# PerfBoard.net
KiCad netlist of a schematic drawn in EAGLE
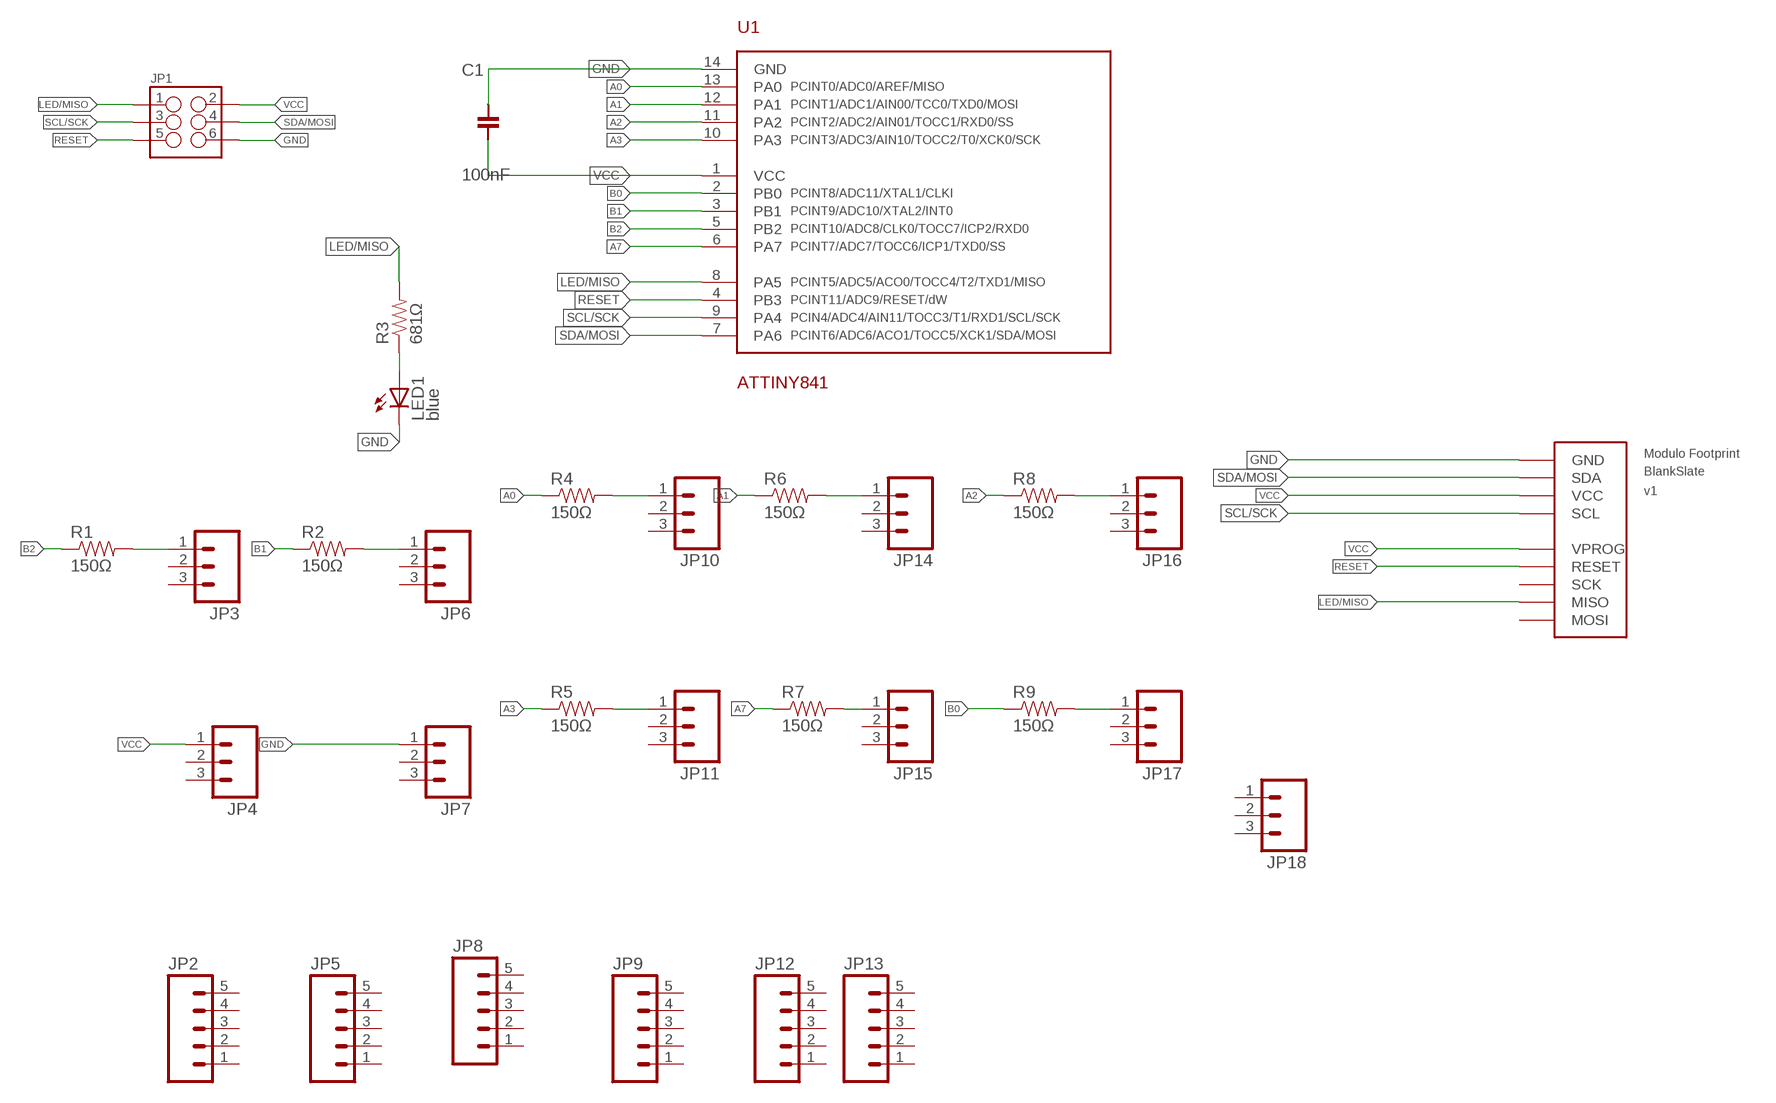
[diagram p0: schematic, sheet 1]

(export (version "E")
  (design (tool "Eeschema 10.0.6"))
  (components
    (comp (ref "C1")
      (value "100nF")
      (footprint "eagle-import:0603")
      (fields (field (name "PARTNUM") "C0603C104K5RACTU"))
      (libsource (lib "eagle-import") (part "CAPACITOR-100NF"))
    )
    (comp (ref "JP1")
      (value "M03X2")
      (footprint "eagle-import:2X3_SMD")
      (libsource (lib "eagle-import") (part "M03X2"))
    )
    (comp (ref "JP2")
      (value "M05NO_SILK")
      (footprint "eagle-import:1X05_NO_SILK")
      (libsource (lib "eagle-import") (part "M05NO_SILK"))
    )
    (comp (ref "JP3")
      (value "M031X03_NO_SILK")
      (footprint "eagle-import:1X03_NO_SILK")
      (libsource (lib "eagle-import") (part "M031X03_NO_SILK"))
    )
    (comp (ref "JP4")
      (value "M031X03_NO_SILK")
      (footprint "eagle-import:1X03_NO_SILK")
      (libsource (lib "eagle-import") (part "M031X03_NO_SILK"))
    )
    (comp (ref "JP5")
      (value "M05NO_SILK")
      (footprint "eagle-import:1X05_NO_SILK")
      (libsource (lib "eagle-import") (part "M05NO_SILK"))
    )
    (comp (ref "JP6")
      (value "M031X03_NO_SILK")
      (footprint "eagle-import:1X03_NO_SILK")
      (libsource (lib "eagle-import") (part "M031X03_NO_SILK"))
    )
    (comp (ref "JP7")
      (value "M031X03_NO_SILK")
      (footprint "eagle-import:1X03_NO_SILK")
      (libsource (lib "eagle-import") (part "M031X03_NO_SILK"))
    )
    (comp (ref "JP8")
      (value "M05NO_SILK")
      (footprint "eagle-import:1X05_NO_SILK")
      (libsource (lib "eagle-import") (part "M05NO_SILK"))
    )
    (comp (ref "JP9")
      (value "M05NO_SILK")
      (footprint "eagle-import:1X05_NO_SILK")
      (libsource (lib "eagle-import") (part "M05NO_SILK"))
    )
    (comp (ref "JP10")
      (value "M031X03_NO_SILK")
      (footprint "eagle-import:1X03_NO_SILK")
      (libsource (lib "eagle-import") (part "M031X03_NO_SILK"))
    )
    (comp (ref "JP11")
      (value "M031X03_NO_SILK")
      (footprint "eagle-import:1X03_NO_SILK")
      (libsource (lib "eagle-import") (part "M031X03_NO_SILK"))
    )
    (comp (ref "JP12")
      (value "M05NO_SILK")
      (footprint "eagle-import:1X05_NO_SILK")
      (libsource (lib "eagle-import") (part "M05NO_SILK"))
    )
    (comp (ref "JP13")
      (value "M05NO_SILK")
      (footprint "eagle-import:1X05_NO_SILK")
      (libsource (lib "eagle-import") (part "M05NO_SILK"))
    )
    (comp (ref "JP14")
      (value "M031X03_NO_SILK")
      (footprint "eagle-import:1X03_NO_SILK")
      (libsource (lib "eagle-import") (part "M031X03_NO_SILK"))
    )
    (comp (ref "JP15")
      (value "M031X03_NO_SILK")
      (footprint "eagle-import:1X03_NO_SILK")
      (libsource (lib "eagle-import") (part "M031X03_NO_SILK"))
    )
    (comp (ref "JP16")
      (value "M031X03_NO_SILK")
      (footprint "eagle-import:1X03_NO_SILK")
      (libsource (lib "eagle-import") (part "M031X03_NO_SILK"))
    )
    (comp (ref "JP17")
      (value "M031X03_NO_SILK")
      (footprint "eagle-import:1X03_NO_SILK")
      (libsource (lib "eagle-import") (part "M031X03_NO_SILK"))
    )
    (comp (ref "JP18")
      (value "M031X03_NO_SILK")
      (footprint "eagle-import:1X03_NO_SILK")
      (libsource (lib "eagle-import") (part "M031X03_NO_SILK"))
    )
    (comp (ref "LED1")
      (value "blue")
      (footprint "eagle-import:0805-LED")
      (fields (field (name "PARTNUM") "LTST-C171TBKT"))
      (libsource (lib "eagle-import") (part "LED-0805-BLUE"))
    )
    (comp (ref "PCB1")
      (value "EXCLUDE")
      (footprint "eagle-import:FOOTPRINT2")
      (fields (field (name "BOARD") "BlankSlate") (field (name "VERSION") "v1"))
      (libsource (lib "eagle-import") (part "FOOTPRINTFOOTPRINT-2"))
    )
    (comp (ref "R1")
      (value "150Ω")
      (footprint "eagle-import:0603")
      (fields (field (name "PARTNUM") "ERJ-3EKF1500V"))
      (libsource (lib "eagle-import") (part "RESISTOR-150Ω"))
    )
    (comp (ref "R2")
      (value "150Ω")
      (footprint "eagle-import:0603")
      (fields (field (name "PARTNUM") "ERJ-3EKF1500V"))
      (libsource (lib "eagle-import") (part "RESISTOR-150Ω"))
    )
    (comp (ref "R3")
      (value "681Ω")
      (footprint "eagle-import:0603")
      (fields (field (name "PARTNUM") "ERJ-3EKF6810V"))
      (libsource (lib "eagle-import") (part "RESISTOR-681Ω"))
    )
    (comp (ref "R4")
      (value "150Ω")
      (footprint "eagle-import:0603")
      (fields (field (name "PARTNUM") "ERJ-3EKF1500V"))
      (libsource (lib "eagle-import") (part "RESISTOR-150Ω"))
    )
    (comp (ref "R5")
      (value "150Ω")
      (footprint "eagle-import:0603")
      (fields (field (name "PARTNUM") "ERJ-3EKF1500V"))
      (libsource (lib "eagle-import") (part "RESISTOR-150Ω"))
    )
    (comp (ref "R6")
      (value "150Ω")
      (footprint "eagle-import:0603")
      (fields (field (name "PARTNUM") "ERJ-3EKF1500V"))
      (libsource (lib "eagle-import") (part "RESISTOR-150Ω"))
    )
    (comp (ref "R7")
      (value "150Ω")
      (footprint "eagle-import:0603")
      (fields (field (name "PARTNUM") "ERJ-3EKF1500V"))
      (libsource (lib "eagle-import") (part "RESISTOR-150Ω"))
    )
    (comp (ref "R8")
      (value "150Ω")
      (footprint "eagle-import:0603")
      (fields (field (name "PARTNUM") "ERJ-3EKF1500V"))
      (libsource (lib "eagle-import") (part "RESISTOR-150Ω"))
    )
    (comp (ref "R9")
      (value "150Ω")
      (footprint "eagle-import:0603")
      (fields (field (name "PARTNUM") "ERJ-3EKF1500V"))
      (libsource (lib "eagle-import") (part "RESISTOR-150Ω"))
    )
    (comp (ref "U1")
      (value "ATTINY841")
      (footprint "eagle-import:SOIC-14")
      (fields (field (name "PARTNUM") "ATTINY841-SSUR"))
      (libsource (lib "eagle-import") (part "ATTINY841"))
    )
  )
  (nets
    (net (code "1") (name "A0") (class "Default")
      (node (ref "R4") (pin "1") (pinfunction "1_1") (pintype "passive"))
      (node (ref "U1") (pin "13") (pinfunction "PA0_13") (pintype "bidirectional"))
    )
    (net (code "2") (name "A1") (class "Default")
      (node (ref "R6") (pin "1") (pinfunction "1_1") (pintype "passive"))
      (node (ref "U1") (pin "12") (pinfunction "PA1_12") (pintype "bidirectional"))
    )
    (net (code "3") (name "A2") (class "Default")
      (node (ref "R8") (pin "1") (pinfunction "1_1") (pintype "passive"))
      (node (ref "U1") (pin "11") (pinfunction "PA2_11") (pintype "bidirectional"))
    )
    (net (code "4") (name "A3") (class "Default")
      (node (ref "R5") (pin "1") (pinfunction "1_1") (pintype "passive"))
      (node (ref "U1") (pin "10") (pinfunction "PA3_10") (pintype "bidirectional"))
    )
    (net (code "5") (name "A7") (class "Default")
      (node (ref "R7") (pin "1") (pinfunction "1_1") (pintype "passive"))
      (node (ref "U1") (pin "6") (pinfunction "PA7_6") (pintype "bidirectional"))
    )
    (net (code "6") (name "B0") (class "Default")
      (node (ref "R9") (pin "1") (pinfunction "1_1") (pintype "passive"))
      (node (ref "U1") (pin "2") (pinfunction "PB0_2") (pintype "bidirectional"))
    )
    (net (code "7") (name "B1") (class "Default")
      (node (ref "R2") (pin "1") (pinfunction "1_1") (pintype "passive"))
      (node (ref "U1") (pin "3") (pinfunction "PB1_3") (pintype "bidirectional"))
    )
    (net (code "8") (name "B2") (class "Default")
      (node (ref "R1") (pin "1") (pinfunction "1_1") (pintype "passive"))
      (node (ref "U1") (pin "5") (pinfunction "PB2_5") (pintype "bidirectional"))
    )
    (net (code "9") (name "GND") (class "Default")
      (node (ref "C1") (pin "1") (pinfunction "1_1") (pintype "passive"))
      (node (ref "JP1") (pin "6") (pinfunction "6_6") (pintype "bidirectional"))
      (node (ref "JP7") (pin "1") (pinfunction "1_1") (pintype "passive"))
      (node (ref "LED1") (pin "C") (pinfunction "C_C") (pintype "passive"))
      (node (ref "PCB1") (pin "BUS0") (pinfunction "GND_BUS0") (pintype "bidirectional"))
      (node (ref "U1") (pin "14") (pinfunction "GND_14") (pintype "bidirectional"))
    )
    (net (code "10") (name "LED{slash}MISO") (class "Default")
      (node (ref "JP1") (pin "1") (pinfunction "1_1") (pintype "bidirectional"))
      (node (ref "PCB1") (pin "PROG3") (pinfunction "MISO_PROG3") (pintype "bidirectional"))
      (node (ref "R3") (pin "2") (pinfunction "2_2") (pintype "passive"))
      (node (ref "U1") (pin "8") (pinfunction "PA5_8") (pintype "bidirectional"))
    )
    (net (code "11") (name "Net-(JP3-Pad1)") (class "Default")
      (node (ref "JP3") (pin "1") (pinfunction "1_1") (pintype "passive"))
      (node (ref "R1") (pin "2") (pinfunction "2_2") (pintype "passive"))
    )
    (net (code "12") (name "Net-(JP6-Pad1)") (class "Default")
      (node (ref "JP6") (pin "1") (pinfunction "1_1") (pintype "passive"))
      (node (ref "R2") (pin "2") (pinfunction "2_2") (pintype "passive"))
    )
    (net (code "13") (name "Net-(JP10-Pad1)") (class "Default")
      (node (ref "JP10") (pin "1") (pinfunction "1_1") (pintype "passive"))
      (node (ref "R4") (pin "2") (pinfunction "2_2") (pintype "passive"))
    )
    (net (code "14") (name "Net-(JP11-Pad1)") (class "Default")
      (node (ref "JP11") (pin "1") (pinfunction "1_1") (pintype "passive"))
      (node (ref "R5") (pin "2") (pinfunction "2_2") (pintype "passive"))
    )
    (net (code "15") (name "Net-(JP14-Pad1)") (class "Default")
      (node (ref "JP14") (pin "1") (pinfunction "1_1") (pintype "passive"))
      (node (ref "R6") (pin "2") (pinfunction "2_2") (pintype "passive"))
    )
    (net (code "16") (name "Net-(JP15-Pad1)") (class "Default")
      (node (ref "JP15") (pin "1") (pinfunction "1_1") (pintype "passive"))
      (node (ref "R7") (pin "2") (pinfunction "2_2") (pintype "passive"))
    )
    (net (code "17") (name "Net-(JP16-Pad1)") (class "Default")
      (node (ref "JP16") (pin "1") (pinfunction "1_1") (pintype "passive"))
      (node (ref "R8") (pin "2") (pinfunction "2_2") (pintype "passive"))
    )
    (net (code "18") (name "Net-(JP17-Pad1)") (class "Default")
      (node (ref "JP17") (pin "1") (pinfunction "1_1") (pintype "passive"))
      (node (ref "R9") (pin "2") (pinfunction "2_2") (pintype "passive"))
    )
    (net (code "19") (name "Net-(LED1-PadA)") (class "Default")
      (node (ref "LED1") (pin "A") (pinfunction "A_A") (pintype "passive"))
      (node (ref "R3") (pin "1") (pinfunction "1_1") (pintype "passive"))
    )
    (net (code "20") (name "RESET") (class "Default")
      (node (ref "JP1") (pin "5") (pinfunction "5_5") (pintype "bidirectional"))
      (node (ref "PCB1") (pin "PROG1") (pinfunction "RESET_PROG1") (pintype "bidirectional"))
      (node (ref "U1") (pin "4") (pinfunction "PB3_4") (pintype "bidirectional"))
    )
    (net (code "21") (name "SCL{slash}SCK") (class "Default")
      (node (ref "JP1") (pin "3") (pinfunction "3_3") (pintype "bidirectional"))
      (node (ref "PCB1") (pin "BUS3") (pinfunction "SCL_BUS3") (pintype "bidirectional"))
      (node (ref "U1") (pin "9") (pinfunction "PA4_9") (pintype "bidirectional"))
    )
    (net (code "22") (name "SDA{slash}MOSI") (class "Default")
      (node (ref "JP1") (pin "4") (pinfunction "4_4") (pintype "bidirectional"))
      (node (ref "PCB1") (pin "BUS1") (pinfunction "SDA_BUS1") (pintype "bidirectional"))
      (node (ref "U1") (pin "7") (pinfunction "PA6_7") (pintype "bidirectional"))
    )
    (net (code "23") (name "VCC") (class "Default")
      (node (ref "C1") (pin "2") (pinfunction "2_2") (pintype "passive"))
      (node (ref "JP1") (pin "2") (pinfunction "2_2") (pintype "bidirectional"))
      (node (ref "JP4") (pin "1") (pinfunction "1_1") (pintype "passive"))
      (node (ref "PCB1") (pin "BUS2") (pinfunction "VCC_BUS2") (pintype "bidirectional"))
      (node (ref "PCB1") (pin "PROG0") (pinfunction "VPROG_PROG0") (pintype "bidirectional"))
      (node (ref "U1") (pin "1") (pinfunction "VCC_1") (pintype "bidirectional"))
    )
    (net (code "24") (name "unconnected-(JP2-Pad1)") (class "Default")
      (node (ref "JP2") (pin "1") (pinfunction "1_1") (pintype "passive"))
    )
    (net (code "25") (name "unconnected-(JP2-Pad2)") (class "Default")
      (node (ref "JP2") (pin "2") (pinfunction "2_2") (pintype "passive"))
    )
    (net (code "26") (name "unconnected-(JP2-Pad3)") (class "Default")
      (node (ref "JP2") (pin "3") (pinfunction "3_3") (pintype "passive"))
    )
    (net (code "27") (name "unconnected-(JP2-Pad4)") (class "Default")
      (node (ref "JP2") (pin "4") (pinfunction "4_4") (pintype "passive"))
    )
    (net (code "28") (name "unconnected-(JP2-Pad5)") (class "Default")
      (node (ref "JP2") (pin "5") (pinfunction "5_5") (pintype "passive"))
    )
    (net (code "29") (name "unconnected-(JP3-Pad2)") (class "Default")
      (node (ref "JP3") (pin "2") (pinfunction "2_2") (pintype "passive"))
    )
    (net (code "30") (name "unconnected-(JP3-Pad3)") (class "Default")
      (node (ref "JP3") (pin "3") (pinfunction "3_3") (pintype "passive"))
    )
    (net (code "31") (name "unconnected-(JP4-Pad2)") (class "Default")
      (node (ref "JP4") (pin "2") (pinfunction "2_2") (pintype "passive"))
    )
    (net (code "32") (name "unconnected-(JP4-Pad3)") (class "Default")
      (node (ref "JP4") (pin "3") (pinfunction "3_3") (pintype "passive"))
    )
    (net (code "33") (name "unconnected-(JP5-Pad1)") (class "Default")
      (node (ref "JP5") (pin "1") (pinfunction "1_1") (pintype "passive"))
    )
    (net (code "34") (name "unconnected-(JP5-Pad2)") (class "Default")
      (node (ref "JP5") (pin "2") (pinfunction "2_2") (pintype "passive"))
    )
    (net (code "35") (name "unconnected-(JP5-Pad3)") (class "Default")
      (node (ref "JP5") (pin "3") (pinfunction "3_3") (pintype "passive"))
    )
    (net (code "36") (name "unconnected-(JP5-Pad4)") (class "Default")
      (node (ref "JP5") (pin "4") (pinfunction "4_4") (pintype "passive"))
    )
    (net (code "37") (name "unconnected-(JP5-Pad5)") (class "Default")
      (node (ref "JP5") (pin "5") (pinfunction "5_5") (pintype "passive"))
    )
    (net (code "38") (name "unconnected-(JP6-Pad2)") (class "Default")
      (node (ref "JP6") (pin "2") (pinfunction "2_2") (pintype "passive"))
    )
    (net (code "39") (name "unconnected-(JP6-Pad3)") (class "Default")
      (node (ref "JP6") (pin "3") (pinfunction "3_3") (pintype "passive"))
    )
    (net (code "40") (name "unconnected-(JP7-Pad2)") (class "Default")
      (node (ref "JP7") (pin "2") (pinfunction "2_2") (pintype "passive"))
    )
    (net (code "41") (name "unconnected-(JP7-Pad3)") (class "Default")
      (node (ref "JP7") (pin "3") (pinfunction "3_3") (pintype "passive"))
    )
    (net (code "42") (name "unconnected-(JP8-Pad1)") (class "Default")
      (node (ref "JP8") (pin "1") (pinfunction "1_1") (pintype "passive"))
    )
    (net (code "43") (name "unconnected-(JP8-Pad2)") (class "Default")
      (node (ref "JP8") (pin "2") (pinfunction "2_2") (pintype "passive"))
    )
    (net (code "44") (name "unconnected-(JP8-Pad3)") (class "Default")
      (node (ref "JP8") (pin "3") (pinfunction "3_3") (pintype "passive"))
    )
    (net (code "45") (name "unconnected-(JP8-Pad4)") (class "Default")
      (node (ref "JP8") (pin "4") (pinfunction "4_4") (pintype "passive"))
    )
    (net (code "46") (name "unconnected-(JP8-Pad5)") (class "Default")
      (node (ref "JP8") (pin "5") (pinfunction "5_5") (pintype "passive"))
    )
    (net (code "47") (name "unconnected-(JP9-Pad1)") (class "Default")
      (node (ref "JP9") (pin "1") (pinfunction "1_1") (pintype "passive"))
    )
    (net (code "48") (name "unconnected-(JP9-Pad2)") (class "Default")
      (node (ref "JP9") (pin "2") (pinfunction "2_2") (pintype "passive"))
    )
    (net (code "49") (name "unconnected-(JP9-Pad3)") (class "Default")
      (node (ref "JP9") (pin "3") (pinfunction "3_3") (pintype "passive"))
    )
    (net (code "50") (name "unconnected-(JP9-Pad4)") (class "Default")
      (node (ref "JP9") (pin "4") (pinfunction "4_4") (pintype "passive"))
    )
    (net (code "51") (name "unconnected-(JP9-Pad5)") (class "Default")
      (node (ref "JP9") (pin "5") (pinfunction "5_5") (pintype "passive"))
    )
    (net (code "52") (name "unconnected-(JP10-Pad2)") (class "Default")
      (node (ref "JP10") (pin "2") (pinfunction "2_2") (pintype "passive"))
    )
    (net (code "53") (name "unconnected-(JP10-Pad3)") (class "Default")
      (node (ref "JP10") (pin "3") (pinfunction "3_3") (pintype "passive"))
    )
    (net (code "54") (name "unconnected-(JP11-Pad2)") (class "Default")
      (node (ref "JP11") (pin "2") (pinfunction "2_2") (pintype "passive"))
    )
    (net (code "55") (name "unconnected-(JP11-Pad3)") (class "Default")
      (node (ref "JP11") (pin "3") (pinfunction "3_3") (pintype "passive"))
    )
    (net (code "56") (name "unconnected-(JP12-Pad1)") (class "Default")
      (node (ref "JP12") (pin "1") (pinfunction "1_1") (pintype "passive"))
    )
    (net (code "57") (name "unconnected-(JP12-Pad2)") (class "Default")
      (node (ref "JP12") (pin "2") (pinfunction "2_2") (pintype "passive"))
    )
    (net (code "58") (name "unconnected-(JP12-Pad3)") (class "Default")
      (node (ref "JP12") (pin "3") (pinfunction "3_3") (pintype "passive"))
    )
    (net (code "59") (name "unconnected-(JP12-Pad4)") (class "Default")
      (node (ref "JP12") (pin "4") (pinfunction "4_4") (pintype "passive"))
    )
    (net (code "60") (name "unconnected-(JP12-Pad5)") (class "Default")
      (node (ref "JP12") (pin "5") (pinfunction "5_5") (pintype "passive"))
    )
    (net (code "61") (name "unconnected-(JP13-Pad1)") (class "Default")
      (node (ref "JP13") (pin "1") (pinfunction "1_1") (pintype "passive"))
    )
    (net (code "62") (name "unconnected-(JP13-Pad2)") (class "Default")
      (node (ref "JP13") (pin "2") (pinfunction "2_2") (pintype "passive"))
    )
    (net (code "63") (name "unconnected-(JP13-Pad3)") (class "Default")
      (node (ref "JP13") (pin "3") (pinfunction "3_3") (pintype "passive"))
    )
    (net (code "64") (name "unconnected-(JP13-Pad4)") (class "Default")
      (node (ref "JP13") (pin "4") (pinfunction "4_4") (pintype "passive"))
    )
    (net (code "65") (name "unconnected-(JP13-Pad5)") (class "Default")
      (node (ref "JP13") (pin "5") (pinfunction "5_5") (pintype "passive"))
    )
    (net (code "66") (name "unconnected-(JP14-Pad2)") (class "Default")
      (node (ref "JP14") (pin "2") (pinfunction "2_2") (pintype "passive"))
    )
    (net (code "67") (name "unconnected-(JP14-Pad3)") (class "Default")
      (node (ref "JP14") (pin "3") (pinfunction "3_3") (pintype "passive"))
    )
    (net (code "68") (name "unconnected-(JP15-Pad2)") (class "Default")
      (node (ref "JP15") (pin "2") (pinfunction "2_2") (pintype "passive"))
    )
    (net (code "69") (name "unconnected-(JP15-Pad3)") (class "Default")
      (node (ref "JP15") (pin "3") (pinfunction "3_3") (pintype "passive"))
    )
    (net (code "70") (name "unconnected-(JP16-Pad2)") (class "Default")
      (node (ref "JP16") (pin "2") (pinfunction "2_2") (pintype "passive"))
    )
    (net (code "71") (name "unconnected-(JP16-Pad3)") (class "Default")
      (node (ref "JP16") (pin "3") (pinfunction "3_3") (pintype "passive"))
    )
    (net (code "72") (name "unconnected-(JP17-Pad2)") (class "Default")
      (node (ref "JP17") (pin "2") (pinfunction "2_2") (pintype "passive"))
    )
    (net (code "73") (name "unconnected-(JP17-Pad3)") (class "Default")
      (node (ref "JP17") (pin "3") (pinfunction "3_3") (pintype "passive"))
    )
    (net (code "74") (name "unconnected-(JP18-Pad1)") (class "Default")
      (node (ref "JP18") (pin "1") (pinfunction "1_1") (pintype "passive"))
    )
    (net (code "75") (name "unconnected-(JP18-Pad2)") (class "Default")
      (node (ref "JP18") (pin "2") (pinfunction "2_2") (pintype "passive"))
    )
    (net (code "76") (name "unconnected-(JP18-Pad3)") (class "Default")
      (node (ref "JP18") (pin "3") (pinfunction "3_3") (pintype "passive"))
    )
    (net (code "77") (name "unconnected-(PCB1-MOSI-PadPROG4)") (class "Default")
      (node (ref "PCB1") (pin "PROG4") (pinfunction "MOSI_PROG4") (pintype "bidirectional"))
    )
    (net (code "78") (name "unconnected-(PCB1-SCK-PadPROG2)") (class "Default")
      (node (ref "PCB1") (pin "PROG2") (pinfunction "SCK_PROG2") (pintype "bidirectional"))
    )
  )
)
